# CAN.net
KiCad netlist of a schematic drawn in Altium Designer
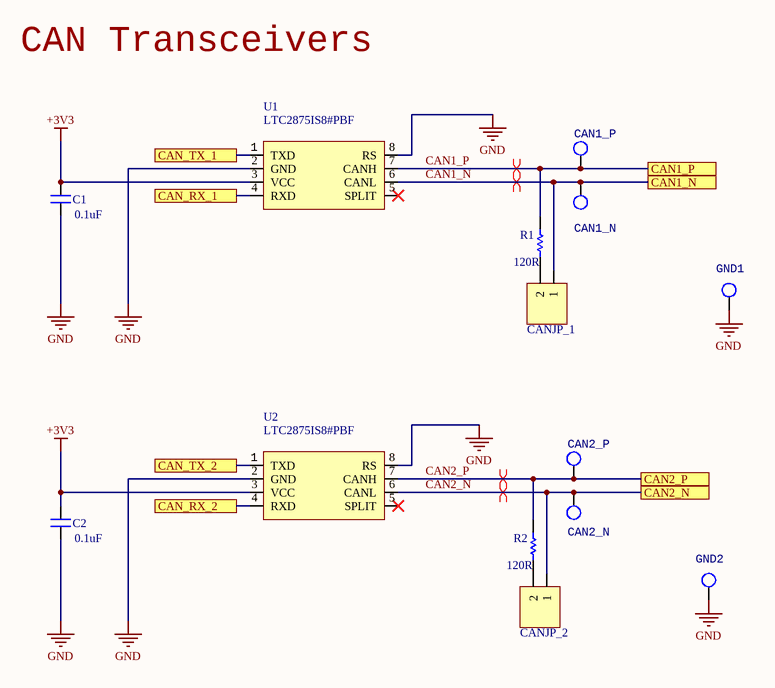
[diagram p0: CAN.SchDoc]

(export (version "E")
  (design (tool "Eeschema 10.0.6"))
  (components
    (comp (ref "C1")
      (value "0.1uF")
      (footprint "CAPC0603(1608)55_N")
      (description "CAP CER 0.1UF 16V X7R 0603")
      (fields (field (name "MPN") "CC0603KRX7R7BB104") (field (name "MANUFACTURER") "Yageo"))
      (libsource (lib "UWRT_Schematic_Library_2020") (part "CAP_0.1uF_16V_0603"))
    )
    (comp (ref "C2")
      (value "0.1uF")
      (footprint "CAPC0603(1608)55_N")
      (description "CAP CER 0.1UF 16V X7R 0603")
      (fields (field (name "MPN") "CC0603KRX7R7BB104") (field (name "MANUFACTURER") "Yageo"))
      (libsource (lib "UWRT_Schematic_Library_2020") (part "CAP_0.1uF_16V_0603"))
    )
    (comp (ref "CAN1_N")
      (value "TESTPOINT_LOOP")
      (footprint "TESTPOINT_LOOP")
      (description "Loop testpoint through-hole pad")
      (fields (field (name "MANUFACTURER") "Keystone Electronics"))
      (libsource (lib "UWRT_Schematic_Library_2020") (part "TESTPOINT_LOOP"))
    )
    (comp (ref "CAN1_P")
      (value "TESTPOINT_LOOP")
      (footprint "TESTPOINT_LOOP")
      (description "Loop testpoint through-hole pad")
      (fields (field (name "MANUFACTURER") "Keystone Electronics"))
      (libsource (lib "UWRT_Schematic_Library_2020") (part "TESTPOINT_LOOP"))
    )
    (comp (ref "CAN2_N")
      (value "TESTPOINT_LOOP")
      (footprint "TESTPOINT_LOOP")
      (description "Loop testpoint through-hole pad")
      (fields (field (name "MANUFACTURER") "Keystone Electronics"))
      (libsource (lib "UWRT_Schematic_Library_2020") (part "TESTPOINT_LOOP"))
    )
    (comp (ref "CAN2_P")
      (value "TESTPOINT_LOOP")
      (footprint "TESTPOINT_LOOP")
      (description "Loop testpoint through-hole pad")
      (fields (field (name "MANUFACTURER") "Keystone Electronics"))
      (libsource (lib "UWRT_Schematic_Library_2020") (part "TESTPOINT_LOOP"))
    )
    (comp (ref "CANJP_1")
      (value "JUMPER_2")
      (footprint "HDR1X2")
      (description "HEADER 2X1")
      (libsource (lib "UWRT_Schematic_Library_2020") (part "JUMPER_2"))
    )
    (comp (ref "CANJP_2")
      (value "JUMPER_2")
      (footprint "HDR1X2")
      (description "HEADER 2X1")
      (libsource (lib "UWRT_Schematic_Library_2020") (part "JUMPER_2"))
    )
    (comp (ref "GND1")
      (value "TESTPOINT_LOOP")
      (footprint "TESTPOINT_LOOP")
      (description "Loop testpoint through-hole pad")
      (fields (field (name "MANUFACTURER") "Keystone Electronics"))
      (libsource (lib "UWRT_Schematic_Library_2020") (part "TESTPOINT_LOOP"))
    )
    (comp (ref "GND2")
      (value "TESTPOINT_LOOP")
      (footprint "TESTPOINT_LOOP")
      (description "Loop testpoint through-hole pad")
      (fields (field (name "MANUFACTURER") "Keystone Electronics"))
      (libsource (lib "UWRT_Schematic_Library_2020") (part "TESTPOINT_LOOP"))
    )
    (comp (ref "R1")
      (value "120R")
      (footprint "RESC0603(1608)_N")
      (description "RES SMD 120 OHM 5% 1/10W 0603")
      (fields (field (name "MANUFACTURER") "Yageo") (field (name "MPN") "RC0603JR-07120RL"))
      (libsource (lib "UWRT_Schematic_Library_2020") (part "RES_120R_0603"))
    )
    (comp (ref "R2")
      (value "120R")
      (footprint "RESC0603(1608)_N")
      (description "RES SMD 120 OHM 5% 1/10W 0603")
      (fields (field (name "MANUFACTURER") "Yageo") (field (name "MPN") "RC0603JR-07120RL"))
      (libsource (lib "UWRT_Schematic_Library_2020") (part "RES_120R_0603"))
    )
    (comp (ref "U1")
      (value "IC TXRX CAN")
      (footprint "LT-S8_N")
      (description "IC TXRX CAN 4MBPS 8SO")
      (fields (field (name "MANUFACTURER") "Linear Technologies") (field (name "MPN") "LTC2875IS8#PBF"))
      (libsource (lib "UWRT_Schematic_Library_2020") (part "LTC2875"))
    )
    (comp (ref "U2")
      (value "IC TXRX CAN")
      (footprint "LT-S8_N")
      (description "IC TXRX CAN 4MBPS 8SO")
      (fields (field (name "MANUFACTURER") "Linear Technologies") (field (name "MPN") "LTC2875IS8#PBF"))
      (libsource (lib "UWRT_Schematic_Library_2020") (part "LTC2875"))
    )
  )
  (nets
    (net (code "1") (name "+3V3") (class "Default")
      (node (ref "C1") (pin "2") (pinfunction "2_2") (pintype "passive"))
      (node (ref "C2") (pin "2") (pinfunction "2_2") (pintype "passive"))
      (node (ref "U1") (pin "3") (pinfunction "VCC_3") (pintype "passive"))
      (node (ref "U2") (pin "3") (pinfunction "VCC_3") (pintype "passive"))
    )
    (net (code "2") (name "/CAN1_N") (class "Default")
      (node (ref "CAN1_N") (pin "1") (pintype "passive"))
      (node (ref "CANJP_1") (pin "1") (pinfunction "1_1") (pintype "passive"))
      (node (ref "U1") (pin "6") (pinfunction "CANL_6") (pintype "passive"))
    )
    (net (code "3") (name "/CAN1_P") (class "Default")
      (node (ref "CAN1_P") (pin "1") (pintype "passive"))
      (node (ref "R1") (pin "1") (pinfunction "1_1") (pintype "passive"))
      (node (ref "U1") (pin "7") (pinfunction "CANH_7") (pintype "passive"))
    )
    (net (code "4") (name "/CAN2_N") (class "Default")
      (node (ref "CAN2_N") (pin "1") (pintype "passive"))
      (node (ref "CANJP_2") (pin "1") (pinfunction "1_1") (pintype "passive"))
      (node (ref "U2") (pin "6") (pinfunction "CANL_6") (pintype "passive"))
    )
    (net (code "5") (name "/CAN2_P") (class "Default")
      (node (ref "CAN2_P") (pin "1") (pintype "passive"))
      (node (ref "R2") (pin "1") (pinfunction "1_1") (pintype "passive"))
      (node (ref "U2") (pin "7") (pinfunction "CANH_7") (pintype "passive"))
    )
    (net (code "6") (name "/CAN_RX_1") (class "Default")
      (node (ref "U1") (pin "4") (pinfunction "RXD_4") (pintype "passive"))
    )
    (net (code "7") (name "/CAN_RX_2") (class "Default")
      (node (ref "U2") (pin "4") (pinfunction "RXD_4") (pintype "passive"))
    )
    (net (code "8") (name "/CAN_TX_1") (class "Default")
      (node (ref "U1") (pin "1") (pinfunction "TXD_1") (pintype "passive"))
    )
    (net (code "9") (name "/CAN_TX_2") (class "Default")
      (node (ref "U2") (pin "1") (pinfunction "TXD_1") (pintype "passive"))
    )
    (net (code "10") (name "GND") (class "Default")
      (node (ref "C1") (pin "1") (pinfunction "1_1") (pintype "passive"))
      (node (ref "C2") (pin "1") (pinfunction "1_1") (pintype "passive"))
      (node (ref "GND1") (pin "1") (pintype "passive"))
      (node (ref "GND2") (pin "1") (pintype "passive"))
      (node (ref "U1") (pin "2") (pinfunction "GND_2") (pintype "passive"))
      (node (ref "U1") (pin "8") (pinfunction "RS_8") (pintype "passive"))
      (node (ref "U2") (pin "2") (pinfunction "GND_2") (pintype "passive"))
      (node (ref "U2") (pin "8") (pinfunction "RS_8") (pintype "passive"))
    )
    (net (code "11") (name "Net-(CANJP_1-Pad2)") (class "Default")
      (node (ref "CANJP_1") (pin "2") (pinfunction "2_2") (pintype "passive"))
      (node (ref "R1") (pin "2") (pinfunction "2_2") (pintype "passive"))
    )
    (net (code "12") (name "Net-(CANJP_2-Pad2)") (class "Default")
      (node (ref "CANJP_2") (pin "2") (pinfunction "2_2") (pintype "passive"))
      (node (ref "R2") (pin "2") (pinfunction "2_2") (pintype "passive"))
    )
    (net (code "13") (name "unconnected-(U1-SPLIT-Pad5)") (class "Default")
      (node (ref "U1") (pin "5") (pinfunction "SPLIT_5") (pintype "passive+no_connect"))
    )
    (net (code "14") (name "unconnected-(U2-SPLIT-Pad5)") (class "Default")
      (node (ref "U2") (pin "5") (pinfunction "SPLIT_5") (pintype "passive+no_connect"))
    )
  )
)
